# Mezzanine.net
KiCad netlist of a schematic drawn in Altium Designer
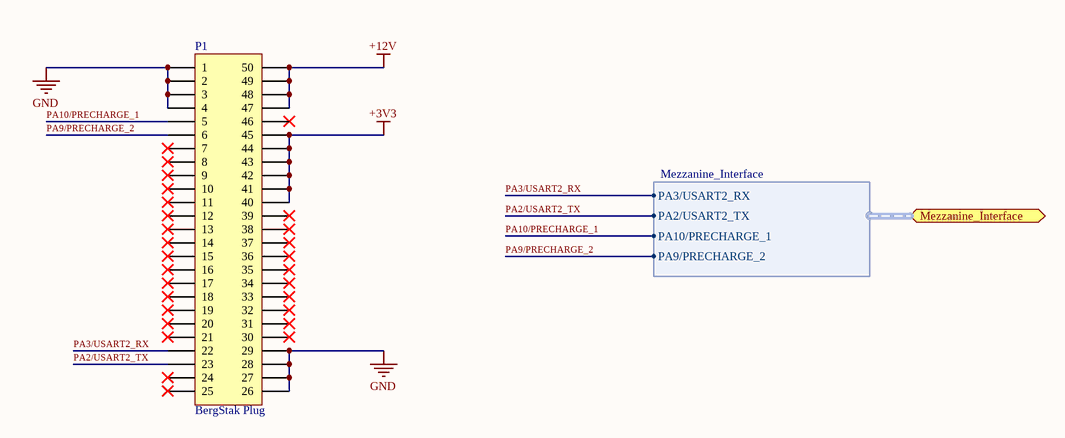
[diagram p0: Mezzanine.SchDoc]

(export (version "E")
  (design (tool "Eeschema 10.0.6"))
  (components
    (comp (ref "P1")
      (value "CONN 50POS Bergstak Plug 0.02\"")
      (footprint "CONN, Bergstak 50 Pos Plug")
      (description "50 Position Connector Plug, Outer Shroud Contacts Surface Mount Gold")
      (fields (field (name "SERIES") "BergStak Plug"))
      (libsource (lib "Schematic Diagrams") (part "CONN 50POS Bergstak Plug 0.02{dblquote}"))
    )
  )
  (nets
    (net (code "2") (name "+3V3") (class "Default")
      (node (ref "P1") (pin "40") (pinfunction "40_40") (pintype "passive"))
      (node (ref "P1") (pin "41") (pinfunction "41_41") (pintype "passive"))
      (node (ref "P1") (pin "42") (pinfunction "42_42") (pintype "passive"))
      (node (ref "P1") (pin "43") (pinfunction "43_43") (pintype "passive"))
      (node (ref "P1") (pin "44") (pinfunction "44_44") (pintype "passive"))
      (node (ref "P1") (pin "45") (pinfunction "45_45") (pintype "passive"))
    )
    (net (code "3") (name "+12V") (class "Default")
      (node (ref "P1") (pin "47") (pinfunction "47_47") (pintype "passive"))
      (node (ref "P1") (pin "48") (pinfunction "48_48") (pintype "passive"))
      (node (ref "P1") (pin "49") (pinfunction "49_49") (pintype "passive"))
      (node (ref "P1") (pin "50") (pinfunction "50_50") (pintype "passive"))
    )
    (net (code "4") (name "/PA2{slash}USART2_TX") (class "Default")
      (node (ref "P1") (pin "23") (pinfunction "23_23") (pintype "passive"))
    )
    (net (code "5") (name "/PA3{slash}USART2_RX") (class "Default")
      (node (ref "P1") (pin "22") (pinfunction "22_22") (pintype "passive"))
    )
    (net (code "6") (name "/PA9{slash}PRECHARGE_2") (class "Default")
      (node (ref "P1") (pin "6") (pinfunction "6_6") (pintype "passive"))
    )
    (net (code "7") (name "/PA10{slash}PRECHARGE_1") (class "Default")
      (node (ref "P1") (pin "5") (pinfunction "5_5") (pintype "passive"))
    )
    (net (code "9") (name "GND") (class "Default")
      (node (ref "P1") (pin "1") (pinfunction "1_1") (pintype "passive"))
      (node (ref "P1") (pin "2") (pinfunction "2_2") (pintype "passive"))
      (node (ref "P1") (pin "26") (pinfunction "26_26") (pintype "passive"))
      (node (ref "P1") (pin "27") (pinfunction "27_27") (pintype "passive"))
      (node (ref "P1") (pin "28") (pinfunction "28_28") (pintype "passive"))
      (node (ref "P1") (pin "29") (pinfunction "29_29") (pintype "passive"))
      (node (ref "P1") (pin "3") (pinfunction "3_3") (pintype "passive"))
      (node (ref "P1") (pin "4") (pinfunction "4_4") (pintype "passive"))
    )
    (net (code "10") (name "unconnected-(P1-Pad7)") (class "Default")
      (node (ref "P1") (pin "7") (pinfunction "7_7") (pintype "passive+no_connect"))
    )
    (net (code "11") (name "unconnected-(P1-Pad8)") (class "Default")
      (node (ref "P1") (pin "8") (pinfunction "8_8") (pintype "passive+no_connect"))
    )
    (net (code "12") (name "unconnected-(P1-Pad9)") (class "Default")
      (node (ref "P1") (pin "9") (pinfunction "9_9") (pintype "passive+no_connect"))
    )
    (net (code "13") (name "unconnected-(P1-Pad10)") (class "Default")
      (node (ref "P1") (pin "10") (pinfunction "10_10") (pintype "passive+no_connect"))
    )
    (net (code "14") (name "unconnected-(P1-Pad11)") (class "Default")
      (node (ref "P1") (pin "11") (pinfunction "11_11") (pintype "passive+no_connect"))
    )
    (net (code "15") (name "unconnected-(P1-Pad12)") (class "Default")
      (node (ref "P1") (pin "12") (pinfunction "12_12") (pintype "passive+no_connect"))
    )
    (net (code "16") (name "unconnected-(P1-Pad13)") (class "Default")
      (node (ref "P1") (pin "13") (pinfunction "13_13") (pintype "passive+no_connect"))
    )
    (net (code "17") (name "unconnected-(P1-Pad14)") (class "Default")
      (node (ref "P1") (pin "14") (pinfunction "14_14") (pintype "passive+no_connect"))
    )
    (net (code "18") (name "unconnected-(P1-Pad15)") (class "Default")
      (node (ref "P1") (pin "15") (pinfunction "15_15") (pintype "passive+no_connect"))
    )
    (net (code "19") (name "unconnected-(P1-Pad16)") (class "Default")
      (node (ref "P1") (pin "16") (pinfunction "16_16") (pintype "passive+no_connect"))
    )
    (net (code "20") (name "unconnected-(P1-Pad17)") (class "Default")
      (node (ref "P1") (pin "17") (pinfunction "17_17") (pintype "passive+no_connect"))
    )
    (net (code "21") (name "unconnected-(P1-Pad18)") (class "Default")
      (node (ref "P1") (pin "18") (pinfunction "18_18") (pintype "passive+no_connect"))
    )
    (net (code "22") (name "unconnected-(P1-Pad19)") (class "Default")
      (node (ref "P1") (pin "19") (pinfunction "19_19") (pintype "passive+no_connect"))
    )
    (net (code "23") (name "unconnected-(P1-Pad20)") (class "Default")
      (node (ref "P1") (pin "20") (pinfunction "20_20") (pintype "passive+no_connect"))
    )
    (net (code "24") (name "unconnected-(P1-Pad21)") (class "Default")
      (node (ref "P1") (pin "21") (pinfunction "21_21") (pintype "passive+no_connect"))
    )
    (net (code "25") (name "unconnected-(P1-Pad24)") (class "Default")
      (node (ref "P1") (pin "24") (pinfunction "24_24") (pintype "passive+no_connect"))
    )
    (net (code "26") (name "unconnected-(P1-Pad25)") (class "Default")
      (node (ref "P1") (pin "25") (pinfunction "25_25") (pintype "passive+no_connect"))
    )
    (net (code "27") (name "unconnected-(P1-Pad30)") (class "Default")
      (node (ref "P1") (pin "30") (pinfunction "30_30") (pintype "passive+no_connect"))
    )
    (net (code "28") (name "unconnected-(P1-Pad31)") (class "Default")
      (node (ref "P1") (pin "31") (pinfunction "31_31") (pintype "passive+no_connect"))
    )
    (net (code "29") (name "unconnected-(P1-Pad32)") (class "Default")
      (node (ref "P1") (pin "32") (pinfunction "32_32") (pintype "passive+no_connect"))
    )
    (net (code "30") (name "unconnected-(P1-Pad33)") (class "Default")
      (node (ref "P1") (pin "33") (pinfunction "33_33") (pintype "passive+no_connect"))
    )
    (net (code "31") (name "unconnected-(P1-Pad34)") (class "Default")
      (node (ref "P1") (pin "34") (pinfunction "34_34") (pintype "passive+no_connect"))
    )
    (net (code "32") (name "unconnected-(P1-Pad35)") (class "Default")
      (node (ref "P1") (pin "35") (pinfunction "35_35") (pintype "passive+no_connect"))
    )
    (net (code "33") (name "unconnected-(P1-Pad36)") (class "Default")
      (node (ref "P1") (pin "36") (pinfunction "36_36") (pintype "passive+no_connect"))
    )
    (net (code "34") (name "unconnected-(P1-Pad37)") (class "Default")
      (node (ref "P1") (pin "37") (pinfunction "37_37") (pintype "passive+no_connect"))
    )
    (net (code "35") (name "unconnected-(P1-Pad38)") (class "Default")
      (node (ref "P1") (pin "38") (pinfunction "38_38") (pintype "passive+no_connect"))
    )
    (net (code "36") (name "unconnected-(P1-Pad39)") (class "Default")
      (node (ref "P1") (pin "39") (pinfunction "39_39") (pintype "passive+no_connect"))
    )
    (net (code "37") (name "unconnected-(P1-Pad46)") (class "Default")
      (node (ref "P1") (pin "46") (pinfunction "46_46") (pintype "passive+no_connect"))
    )
  )
)
